# 293_01.net
KiCad netlist of a schematic drawn in EAGLE
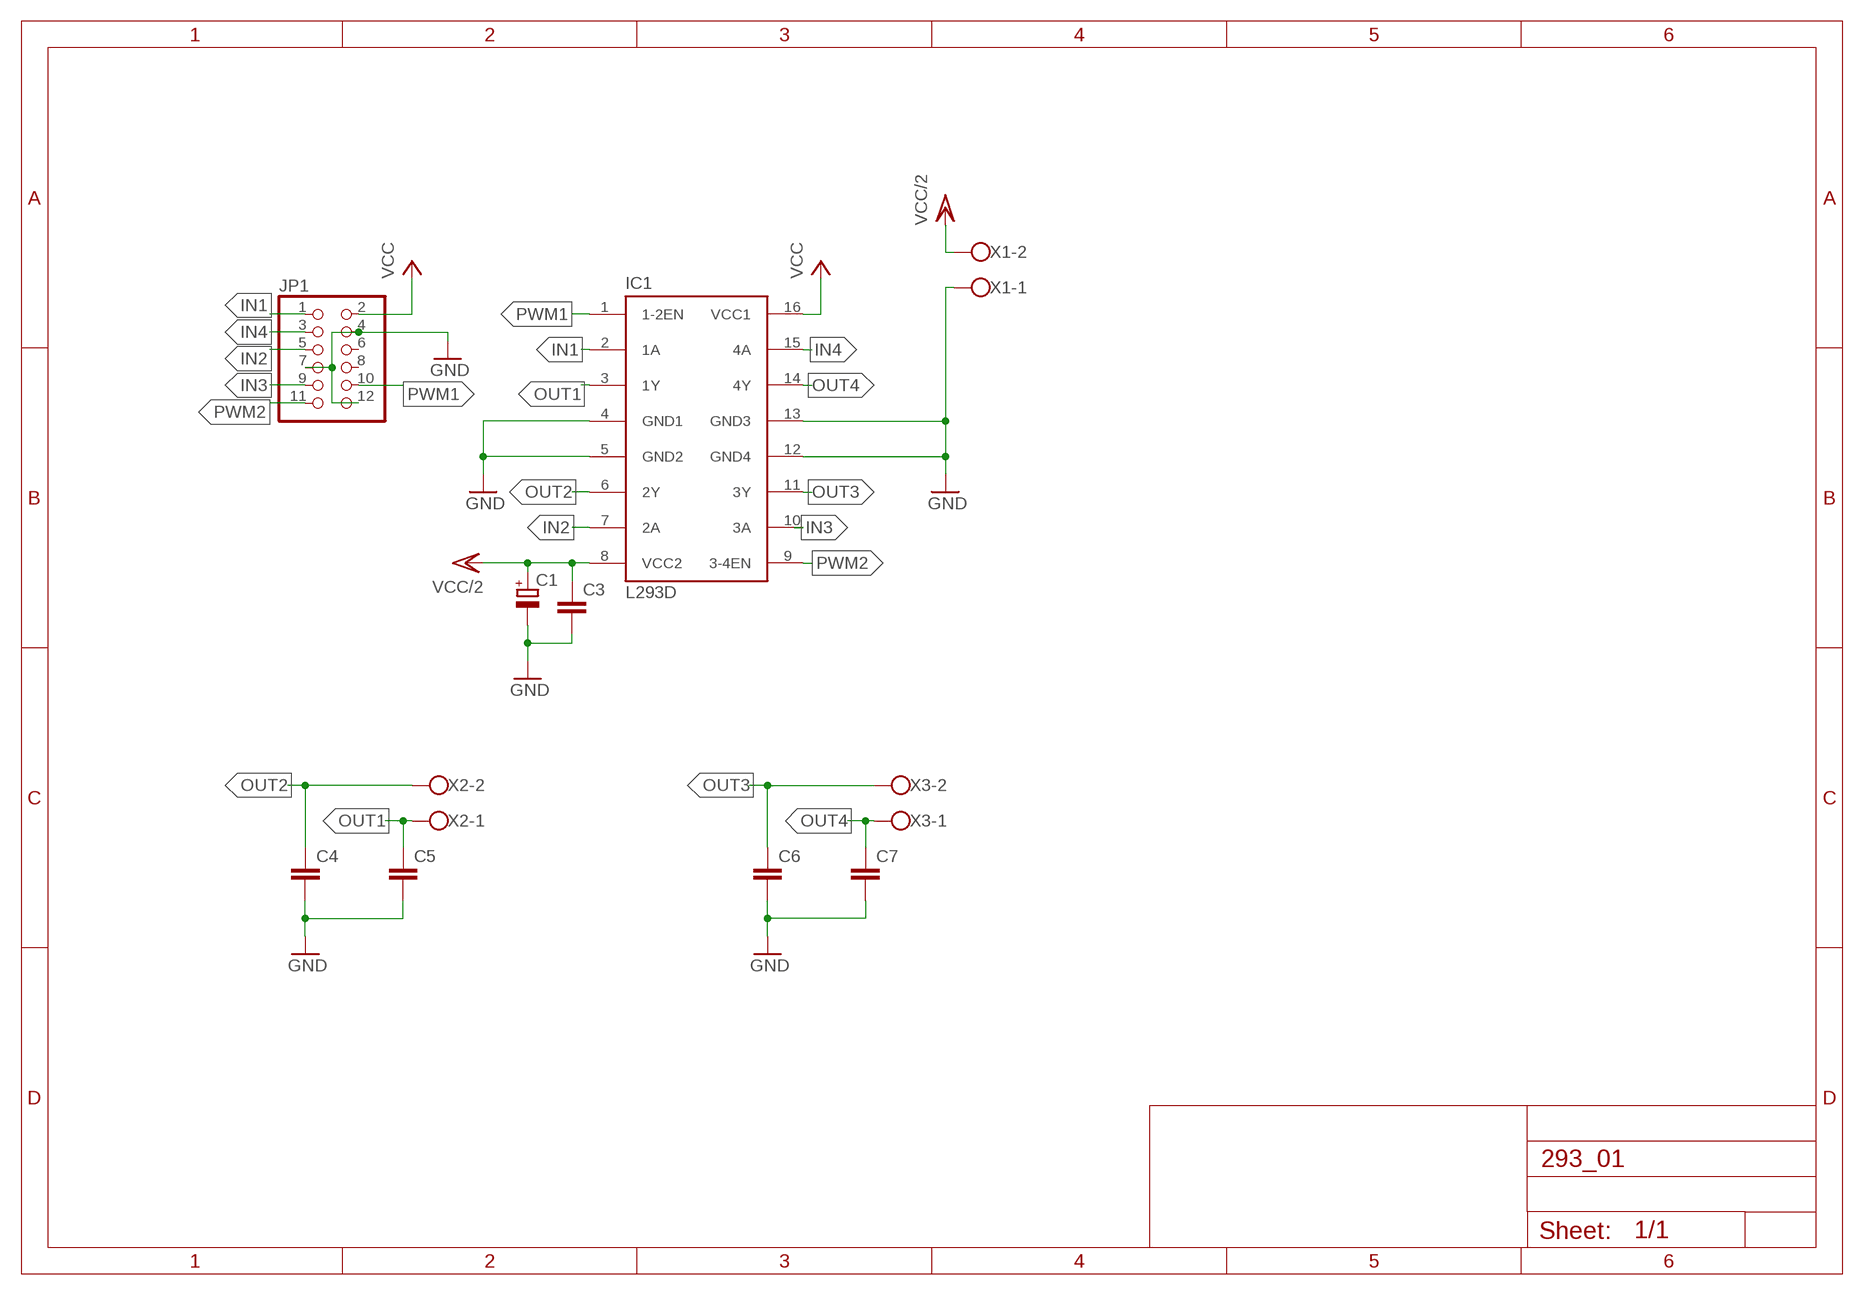
[diagram p0: schematic, sheet 1]

(export (version "E")
  (design (tool "Eeschema 10.0.6"))
  (components
    (comp (ref "C1")
      (value "CPOL-EUE2.5-7")
      (footprint "eagle-import:E2,5-7")
      (libsource (lib "eagle-import") (part "CPOL-EUE2.5-7"))
    )
    (comp (ref "C3")
      (value "C-EUC1206")
      (footprint "eagle-import:C1206")
      (libsource (lib "eagle-import") (part "C-EUC1206"))
    )
    (comp (ref "C4")
      (value "C-EUC1206")
      (footprint "eagle-import:C1206")
      (libsource (lib "eagle-import") (part "C-EUC1206"))
    )
    (comp (ref "C5")
      (value "C-EUC1206")
      (footprint "eagle-import:C1206")
      (libsource (lib "eagle-import") (part "C-EUC1206"))
    )
    (comp (ref "C6")
      (value "C-EUC1206")
      (footprint "eagle-import:C1206")
      (libsource (lib "eagle-import") (part "C-EUC1206"))
    )
    (comp (ref "C7")
      (value "C-EUC1206")
      (footprint "eagle-import:C1206")
      (libsource (lib "eagle-import") (part "C-EUC1206"))
    )
    (comp (ref "IC1")
      (value "L293D")
      (footprint "eagle-import:DIL16")
      (libsource (lib "eagle-import") (part "L293D"))
    )
    (comp (ref "JP1")
      (value "PINHD-2X6")
      (footprint "eagle-import:2X06")
      (libsource (lib "eagle-import") (part "PINHD-2X6"))
    )
    (comp (ref "X1")
      (value "W237-102")
      (footprint "eagle-import:W237-102")
      (fields (field (name "MPN") "237-102"))
      (libsource (lib "eagle-import") (part "W237-102"))
    )
    (comp (ref "X2")
      (value "W237-102")
      (footprint "eagle-import:W237-102")
      (fields (field (name "MPN") "237-102"))
      (libsource (lib "eagle-import") (part "W237-102"))
    )
    (comp (ref "X3")
      (value "W237-102")
      (footprint "eagle-import:W237-102")
      (fields (field (name "MPN") "237-102"))
      (libsource (lib "eagle-import") (part "W237-102"))
    )
  )
  (nets
    (net (code "1") (name "GND") (class "Default")
      (node (ref "C1") (pin "-") (pinfunction "-_-") (pintype "passive"))
      (node (ref "C3") (pin "2") (pinfunction "2_2") (pintype "passive"))
      (node (ref "C4") (pin "2") (pinfunction "2_2") (pintype "passive"))
      (node (ref "C5") (pin "2") (pinfunction "2_2") (pintype "passive"))
      (node (ref "C6") (pin "2") (pinfunction "2_2") (pintype "passive"))
      (node (ref "C7") (pin "2") (pinfunction "2_2") (pintype "passive"))
      (node (ref "IC1") (pin "12") (pinfunction "GND4_12") (pintype "power_in"))
      (node (ref "IC1") (pin "13") (pinfunction "GND3_13") (pintype "power_in"))
      (node (ref "IC1") (pin "4") (pinfunction "GND1_4") (pintype "power_in"))
      (node (ref "IC1") (pin "5") (pinfunction "GND2_5") (pintype "power_in"))
      (node (ref "JP1") (pin "12") (pinfunction "12_12") (pintype "passive"))
      (node (ref "JP1") (pin "4") (pinfunction "4_4") (pintype "passive"))
      (node (ref "JP1") (pin "7") (pinfunction "7_7") (pintype "passive"))
      (node (ref "X1") (pin "1") (pinfunction "KL_1") (pintype "passive"))
    )
    (net (code "2") (name "IN1") (class "Default")
      (node (ref "IC1") (pin "2") (pinfunction "1A_2") (pintype "input"))
      (node (ref "JP1") (pin "1") (pinfunction "1_1") (pintype "passive"))
    )
    (net (code "3") (name "IN2") (class "Default")
      (node (ref "IC1") (pin "7") (pinfunction "2A_7") (pintype "input"))
      (node (ref "JP1") (pin "5") (pinfunction "5_5") (pintype "passive"))
    )
    (net (code "4") (name "IN3") (class "Default")
      (node (ref "IC1") (pin "10") (pinfunction "3A_10") (pintype "input"))
      (node (ref "JP1") (pin "9") (pinfunction "9_9") (pintype "passive"))
    )
    (net (code "5") (name "IN4") (class "Default")
      (node (ref "IC1") (pin "15") (pinfunction "4A_15") (pintype "input"))
      (node (ref "JP1") (pin "3") (pinfunction "3_3") (pintype "passive"))
    )
    (net (code "6") (name "OUT1") (class "Default")
      (node (ref "C5") (pin "1") (pinfunction "1_1") (pintype "passive"))
      (node (ref "IC1") (pin "3") (pinfunction "1Y_3") (pintype "output"))
      (node (ref "X2") (pin "1") (pinfunction "KL_1") (pintype "passive"))
    )
    (net (code "7") (name "OUT2") (class "Default")
      (node (ref "C4") (pin "1") (pinfunction "1_1") (pintype "passive"))
      (node (ref "IC1") (pin "6") (pinfunction "2Y_6") (pintype "output"))
      (node (ref "X2") (pin "2") (pinfunction "KL_2") (pintype "passive"))
    )
    (net (code "8") (name "OUT3") (class "Default")
      (node (ref "C6") (pin "1") (pinfunction "1_1") (pintype "passive"))
      (node (ref "IC1") (pin "11") (pinfunction "3Y_11") (pintype "output"))
      (node (ref "X3") (pin "2") (pinfunction "KL_2") (pintype "passive"))
    )
    (net (code "9") (name "OUT4") (class "Default")
      (node (ref "C7") (pin "1") (pinfunction "1_1") (pintype "passive"))
      (node (ref "IC1") (pin "14") (pinfunction "4Y_14") (pintype "output"))
      (node (ref "X3") (pin "1") (pinfunction "KL_1") (pintype "passive"))
    )
    (net (code "10") (name "PWM1") (class "Default")
      (node (ref "IC1") (pin "1") (pinfunction "1-2EN_1") (pintype "input"))
      (node (ref "JP1") (pin "10") (pinfunction "10_10") (pintype "passive"))
    )
    (net (code "11") (name "PWM2") (class "Default")
      (node (ref "IC1") (pin "9") (pinfunction "3-4EN_9") (pintype "input"))
      (node (ref "JP1") (pin "11") (pinfunction "11_11") (pintype "passive"))
    )
    (net (code "12") (name "VCC") (class "Default")
      (node (ref "IC1") (pin "16") (pinfunction "VCC1_16") (pintype "power_in"))
      (node (ref "JP1") (pin "2") (pinfunction "2_2") (pintype "passive"))
    )
    (net (code "13") (name "VCC{slash}2") (class "Default")
      (node (ref "C1") (pin "+") (pinfunction "+_+") (pintype "passive"))
      (node (ref "C3") (pin "1") (pinfunction "1_1") (pintype "passive"))
      (node (ref "IC1") (pin "8") (pinfunction "VCC2_8") (pintype "power_in"))
      (node (ref "X1") (pin "2") (pinfunction "KL_2") (pintype "passive"))
    )
    (net (code "14") (name "unconnected-(JP1-Pad6)") (class "Default")
      (node (ref "JP1") (pin "6") (pinfunction "6_6") (pintype "passive"))
    )
    (net (code "15") (name "unconnected-(JP1-Pad8)") (class "Default")
      (node (ref "JP1") (pin "8") (pinfunction "8_8") (pintype "passive"))
    )
  )
)
